# RF24_Node.net
KiCad netlist of a schematic drawn in EAGLE
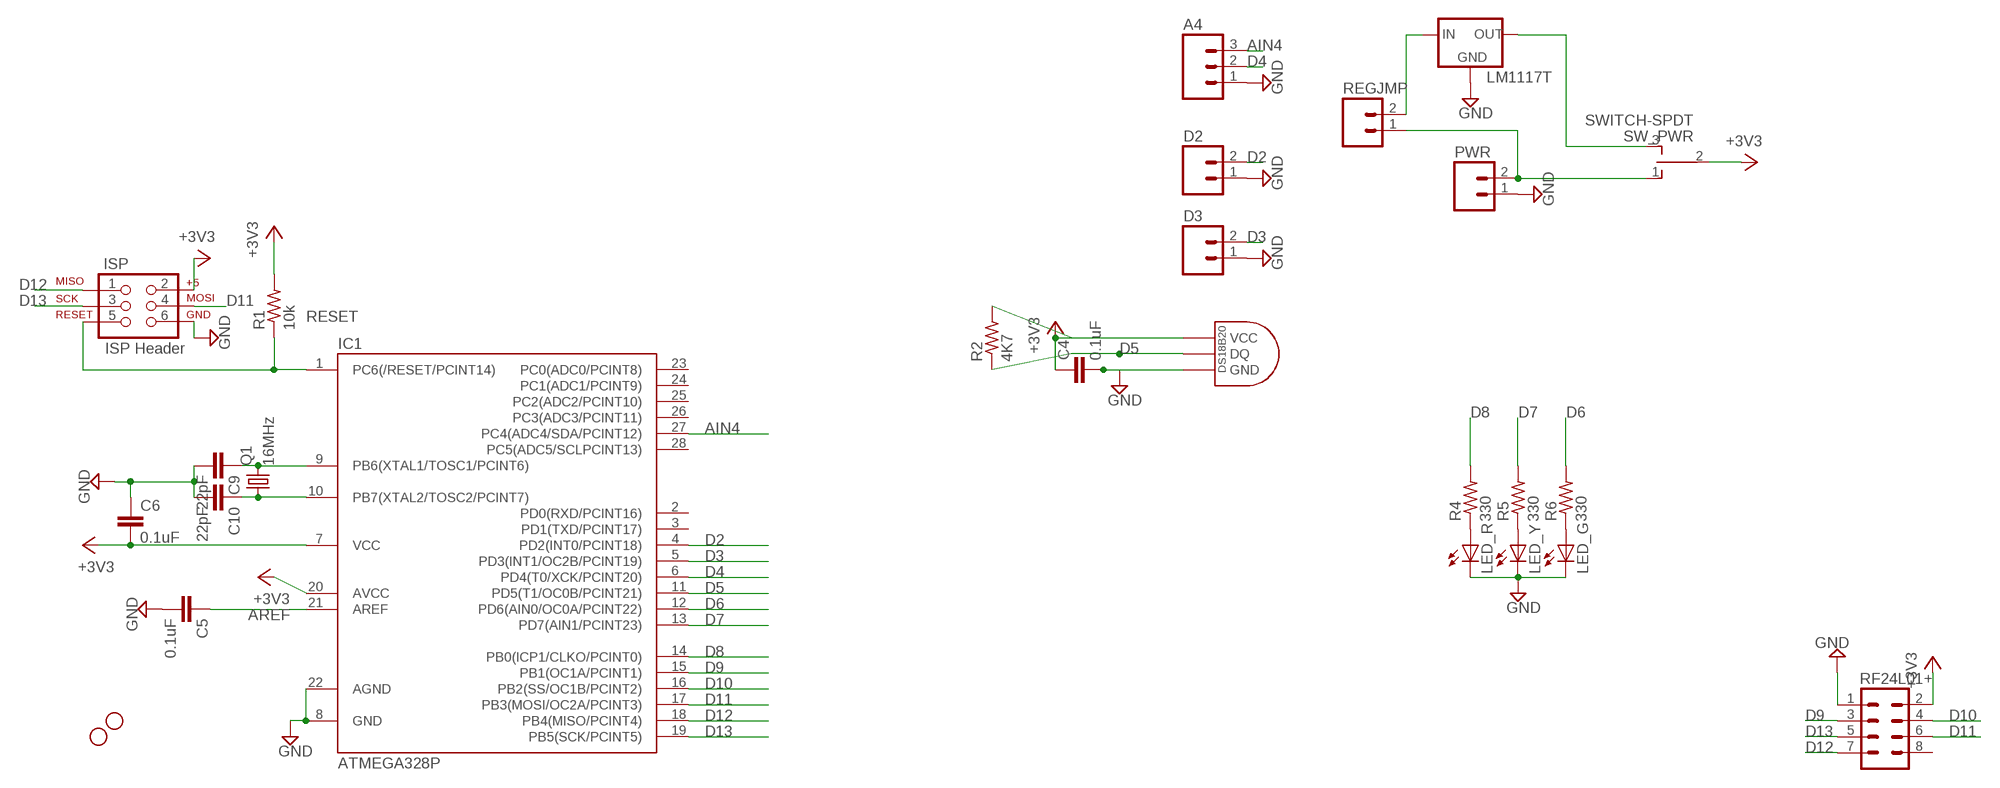
[diagram p0: schematic, sheet 1]

(export (version "E")
  (design (tool "Eeschema 10.0.6"))
  (components
    (comp (ref "A4")
      (value "M03PTH")
      (footprint "eagle-import:1X03")
      (libsource (lib "eagle-import") (part "M03PTH"))
    )
    (comp (ref "C4")
      (value "0.1uF")
      (footprint "eagle-import:C025-025X050")
      (libsource (lib "eagle-import") (part "C-EU025-025X050"))
    )
    (comp (ref "C5")
      (value "0.1uF")
      (footprint "eagle-import:C025-025X050")
      (libsource (lib "eagle-import") (part "C-EU025-025X050"))
    )
    (comp (ref "C6")
      (value "0.1uF")
      (footprint "eagle-import:C025-025X050")
      (libsource (lib "eagle-import") (part "C-EU025-025X050"))
    )
    (comp (ref "C9")
      (value "22pF")
      (footprint "eagle-import:C025-025X050")
      (libsource (lib "eagle-import") (part "C-EU025-025X050"))
    )
    (comp (ref "C10")
      (value "22pF")
      (footprint "eagle-import:C025-025X050")
      (libsource (lib "eagle-import") (part "C-EU025-025X050"))
    )
    (comp (ref "D2")
      (value "M02PTH")
      (footprint "eagle-import:1X02")
      (libsource (lib "eagle-import") (part "M02PTH"))
    )
    (comp (ref "D3")
      (value "M02PTH")
      (footprint "eagle-import:1X02")
      (libsource (lib "eagle-import") (part "M02PTH"))
    )
    (comp (ref "DS18B20")
      (value "DS1820TO92")
      (footprint "eagle-import:DS1820")
      (libsource (lib "eagle-import") (part "DS1820TO92"))
    )
    (comp (ref "IC1")
      (value "ATMEGA328P")
      (footprint "eagle-import:DIL28-3")
      (libsource (lib "eagle-import") (part "ATMEGA48/88/168-PU"))
    )
    (comp (ref "ISP")
      (value "ISP Header")
      (footprint "eagle-import:2X3")
      (libsource (lib "eagle-import") (part "AVR_SPI_PRG_6PTH"))
    )
    (comp (ref "JP2")
      (value "STAND-OFF")
      (footprint "eagle-import:STAND-OFF")
      (libsource (lib "eagle-import") (part "STAND-OFF"))
    )
    (comp (ref "JP8")
      (value "STAND-OFF")
      (footprint "eagle-import:STAND-OFF")
      (libsource (lib "eagle-import") (part "STAND-OFF"))
    )
    (comp (ref "LED_G")
      (value "LED3MM")
      (footprint "eagle-import:LED3MM")
      (libsource (lib "eagle-import") (part "LED3MM"))
    )
    (comp (ref "LED_R")
      (value "LED3MM")
      (footprint "eagle-import:LED3MM")
      (libsource (lib "eagle-import") (part "LED3MM"))
    )
    (comp (ref "LED_Y")
      (value "LED3MM")
      (footprint "eagle-import:LED3MM")
      (libsource (lib "eagle-import") (part "LED3MM"))
    )
    (comp (ref "LM1117T")
      (value "LM1117T-3.3-V")
      (footprint "eagle-import:TO220V")
      (libsource (lib "eagle-import") (part "LM1117T--V3.3"))
    )
    (comp (ref "PWR")
      (value "M02PTH")
      (footprint "eagle-import:1X02")
      (libsource (lib "eagle-import") (part "M02PTH"))
    )
    (comp (ref "Q1")
      (value "16MHz")
      (footprint "eagle-import:HC49_S")
      (libsource (lib "eagle-import") (part "CRYSTALHC49S"))
    )
    (comp (ref "R1")
      (value "10k")
      (footprint "eagle-import:0204V")
      (libsource (lib "eagle-import") (part "R-US_0204/2V"))
    )
    (comp (ref "R2")
      (value "4K7")
      (footprint "eagle-import:0204V")
      (libsource (lib "eagle-import") (part "R-US_0204/2V"))
    )
    (comp (ref "R4")
      (value "330")
      (footprint "eagle-import:0204V")
      (libsource (lib "eagle-import") (part "R-US_0204/2V"))
    )
    (comp (ref "R5")
      (value "330")
      (footprint "eagle-import:0204V")
      (libsource (lib "eagle-import") (part "R-US_0204/2V"))
    )
    (comp (ref "R6")
      (value "330")
      (footprint "eagle-import:0204V")
      (libsource (lib "eagle-import") (part "R-US_0204/2V"))
    )
    (comp (ref "REGJMP")
      (value "M02PTH")
      (footprint "eagle-import:1X02")
      (libsource (lib "eagle-import") (part "M02PTH"))
    )
    (comp (ref "RF24L01+")
      (value "M04X2")
      (footprint "eagle-import:2X4")
      (libsource (lib "eagle-import") (part "M04X2"))
    )
    (comp (ref "SW_PWR")
      (value "SWITCH-SPDT")
      (footprint "eagle-import:OS102011MS2QN1")
      (libsource (lib "eagle-import") (part "SWITCH-SPDT"))
    )
  )
  (nets
    (net (code "1") (name "+3V3") (class "Default")
      (node (ref "C4") (pin "1") (pinfunction "1_1") (pintype "passive"))
      (node (ref "C6") (pin "2") (pinfunction "2_2") (pintype "passive"))
      (node (ref "DS18B20") (pin "VDD") (pinfunction "VCC_VDD") (pintype "power_in"))
      (node (ref "IC1") (pin "20") (pinfunction "AVCC_20") (pintype "passive"))
      (node (ref "IC1") (pin "7") (pinfunction "VCC_7") (pintype "power_in"))
      (node (ref "ISP") (pin "2") (pinfunction "2_2") (pintype "passive"))
      (node (ref "R1") (pin "2") (pinfunction "2_2") (pintype "passive"))
      (node (ref "R2") (pin "2") (pinfunction "2_2") (pintype "passive"))
      (node (ref "RF24L01+") (pin "2") (pinfunction "2_2") (pintype "passive"))
      (node (ref "SW_PWR") (pin "2") (pinfunction "P_2") (pintype "passive"))
    )
    (net (code "2") (name "/AIN4") (class "Default")
      (node (ref "A4") (pin "3") (pinfunction "3_3") (pintype "passive"))
      (node (ref "IC1") (pin "27") (pinfunction "PC4(ADC4/SDA/PCINT12)_27") (pintype "bidirectional"))
    )
    (net (code "3") (name "/AREF") (class "Default")
      (node (ref "C5") (pin "1") (pinfunction "1_1") (pintype "passive"))
      (node (ref "IC1") (pin "21") (pinfunction "AREF_21") (pintype "passive"))
    )
    (net (code "4") (name "/D2") (class "Default")
      (node (ref "D2") (pin "2") (pinfunction "2_2") (pintype "passive"))
      (node (ref "IC1") (pin "4") (pinfunction "PD2(INT0/PCINT18)_4") (pintype "bidirectional"))
    )
    (net (code "5") (name "/D3") (class "Default")
      (node (ref "D3") (pin "2") (pinfunction "2_2") (pintype "passive"))
      (node (ref "IC1") (pin "5") (pinfunction "PD3(INT1/OC2B/PCINT19)_5") (pintype "bidirectional"))
    )
    (net (code "6") (name "/D4") (class "Default")
      (node (ref "A4") (pin "2") (pinfunction "2_2") (pintype "passive"))
      (node (ref "IC1") (pin "6") (pinfunction "PD4(T0/XCK/PCINT20)_6") (pintype "bidirectional"))
    )
    (net (code "7") (name "/D5") (class "Default")
      (node (ref "DS18B20") (pin "DQ") (pinfunction "DQ_DQ") (pintype "bidirectional"))
      (node (ref "IC1") (pin "11") (pinfunction "PD5(T1/OC0B/PCINT21)_11") (pintype "bidirectional"))
      (node (ref "R2") (pin "1") (pinfunction "1_1") (pintype "passive"))
    )
    (net (code "8") (name "/D6") (class "Default")
      (node (ref "IC1") (pin "12") (pinfunction "PD6(AIN0/OC0A/PCINT22)_12") (pintype "bidirectional"))
      (node (ref "R6") (pin "2") (pinfunction "2_2") (pintype "passive"))
    )
    (net (code "9") (name "/D7") (class "Default")
      (node (ref "IC1") (pin "13") (pinfunction "PD7(AIN1/PCINT23)_13") (pintype "bidirectional"))
      (node (ref "R5") (pin "2") (pinfunction "2_2") (pintype "passive"))
    )
    (net (code "10") (name "/D8") (class "Default")
      (node (ref "IC1") (pin "14") (pinfunction "PB0(ICP1/CLKO/PCINT0)_14") (pintype "bidirectional"))
      (node (ref "R4") (pin "2") (pinfunction "2_2") (pintype "passive"))
    )
    (net (code "11") (name "/D9") (class "Default")
      (node (ref "IC1") (pin "15") (pinfunction "PB1(OC1A/PCINT1)_15") (pintype "bidirectional"))
      (node (ref "RF24L01+") (pin "3") (pinfunction "3_3") (pintype "passive"))
    )
    (net (code "12") (name "/D10") (class "Default")
      (node (ref "IC1") (pin "16") (pinfunction "PB2(SS/OC1B/PCINT2)_16") (pintype "bidirectional"))
      (node (ref "RF24L01+") (pin "4") (pinfunction "4_4") (pintype "passive"))
    )
    (net (code "13") (name "/D11") (class "Default")
      (node (ref "IC1") (pin "17") (pinfunction "PB3(MOSI/OC2A/PCINT3)_17") (pintype "bidirectional"))
      (node (ref "ISP") (pin "4") (pinfunction "4_4") (pintype "passive"))
      (node (ref "RF24L01+") (pin "6") (pinfunction "6_6") (pintype "passive"))
    )
    (net (code "14") (name "/D12") (class "Default")
      (node (ref "IC1") (pin "18") (pinfunction "PB4(MISO/PCINT4)_18") (pintype "bidirectional"))
      (node (ref "ISP") (pin "1") (pinfunction "1_1") (pintype "passive"))
      (node (ref "RF24L01+") (pin "7") (pinfunction "7_7") (pintype "passive"))
    )
    (net (code "15") (name "/D13") (class "Default")
      (node (ref "IC1") (pin "19") (pinfunction "PB5(SCK/PCINT5)_19") (pintype "bidirectional"))
      (node (ref "ISP") (pin "3") (pinfunction "3_3") (pintype "passive"))
      (node (ref "RF24L01+") (pin "5") (pinfunction "5_5") (pintype "passive"))
    )
    (net (code "16") (name "/RESET") (class "Default")
      (node (ref "IC1") (pin "1") (pinfunction "PC6(/RESET/PCINT14)_1") (pintype "bidirectional"))
      (node (ref "ISP") (pin "5") (pinfunction "5_5") (pintype "passive"))
      (node (ref "R1") (pin "1") (pinfunction "1_1") (pintype "passive"))
    )
    (net (code "17") (name "GND") (class "Default")
      (node (ref "A4") (pin "1") (pinfunction "1_1") (pintype "passive"))
      (node (ref "C10") (pin "2") (pinfunction "2_2") (pintype "passive"))
      (node (ref "C4") (pin "2") (pinfunction "2_2") (pintype "passive"))
      (node (ref "C5") (pin "2") (pinfunction "2_2") (pintype "passive"))
      (node (ref "C6") (pin "1") (pinfunction "1_1") (pintype "passive"))
      (node (ref "C9") (pin "2") (pinfunction "2_2") (pintype "passive"))
      (node (ref "D2") (pin "1") (pinfunction "1_1") (pintype "passive"))
      (node (ref "D3") (pin "1") (pinfunction "1_1") (pintype "passive"))
      (node (ref "DS18B20") (pin "GND") (pinfunction "GND_GND") (pintype "power_in"))
      (node (ref "IC1") (pin "22") (pinfunction "AGND_22") (pintype "power_in"))
      (node (ref "IC1") (pin "8") (pinfunction "GND_8") (pintype "power_in"))
      (node (ref "ISP") (pin "6") (pinfunction "6_6") (pintype "passive"))
      (node (ref "LED_G") (pin "K") (pinfunction "C_K") (pintype "passive"))
      (node (ref "LED_R") (pin "K") (pinfunction "C_K") (pintype "passive"))
      (node (ref "LED_Y") (pin "K") (pinfunction "C_K") (pintype "passive"))
      (node (ref "LM1117T") (pin "1") (pinfunction "GND_1") (pintype "input"))
      (node (ref "PWR") (pin "1") (pinfunction "1_1") (pintype "passive"))
      (node (ref "RF24L01+") (pin "1") (pinfunction "1_1") (pintype "passive"))
    )
    (net (code "18") (name "Net-(IC1-PB6(XTAL1{slash}TOSC1{slash}PCINT6))") (class "Default")
      (node (ref "C9") (pin "1") (pinfunction "1_1") (pintype "passive"))
      (node (ref "IC1") (pin "9") (pinfunction "PB6(XTAL1/TOSC1/PCINT6)_9") (pintype "bidirectional"))
      (node (ref "Q1") (pin "2") (pinfunction "2_2") (pintype "passive"))
    )
    (net (code "19") (name "Net-(IC1-PB7(XTAL2{slash}TOSC2{slash}PCINT7))") (class "Default")
      (node (ref "C10") (pin "1") (pinfunction "1_1") (pintype "passive"))
      (node (ref "IC1") (pin "10") (pinfunction "PB7(XTAL2/TOSC2/PCINT7)_10") (pintype "bidirectional"))
      (node (ref "Q1") (pin "1") (pinfunction "1_1") (pintype "passive"))
    )
    (net (code "20") (name "Net-(LED_G-PadA)") (class "Default")
      (node (ref "LED_G") (pin "A") (pinfunction "A_A") (pintype "passive"))
      (node (ref "R6") (pin "1") (pinfunction "1_1") (pintype "passive"))
    )
    (net (code "21") (name "Net-(LED_R-PadA)") (class "Default")
      (node (ref "LED_R") (pin "A") (pinfunction "A_A") (pintype "passive"))
      (node (ref "R4") (pin "1") (pinfunction "1_1") (pintype "passive"))
    )
    (net (code "22") (name "Net-(LED_Y-PadA)") (class "Default")
      (node (ref "LED_Y") (pin "A") (pinfunction "A_A") (pintype "passive"))
      (node (ref "R5") (pin "1") (pinfunction "1_1") (pintype "passive"))
    )
    (net (code "23") (name "Net-(LM1117T-IN)") (class "Default")
      (node (ref "LM1117T") (pin "3") (pinfunction "IN_3") (pintype "input"))
      (node (ref "REGJMP") (pin "2") (pinfunction "2_2") (pintype "passive"))
    )
    (net (code "24") (name "Net-(LM1117T-OUT)") (class "Default")
      (node (ref "LM1117T") (pin "2") (pinfunction "OUT_2") (pintype "passive"))
      (node (ref "SW_PWR") (pin "3") (pinfunction "S_3") (pintype "passive"))
    )
    (net (code "25") (name "Net-(SW_PWR-O)") (class "Default")
      (node (ref "PWR") (pin "2") (pinfunction "2_2") (pintype "passive"))
      (node (ref "REGJMP") (pin "1") (pinfunction "1_1") (pintype "passive"))
      (node (ref "SW_PWR") (pin "1") (pinfunction "O_1") (pintype "passive"))
    )
    (net (code "26") (name "unconnected-(IC1-PC0(ADC0{slash}PCINT8)-Pad23)") (class "Default")
      (node (ref "IC1") (pin "23") (pinfunction "PC0(ADC0/PCINT8)_23") (pintype "bidirectional"))
    )
    (net (code "27") (name "unconnected-(IC1-PC1(ADC1{slash}PCINT9)-Pad24)") (class "Default")
      (node (ref "IC1") (pin "24") (pinfunction "PC1(ADC1/PCINT9)_24") (pintype "bidirectional"))
    )
    (net (code "28") (name "unconnected-(IC1-PC2(ADC2{slash}PCINT10)-Pad25)") (class "Default")
      (node (ref "IC1") (pin "25") (pinfunction "PC2(ADC2/PCINT10)_25") (pintype "bidirectional"))
    )
    (net (code "29") (name "unconnected-(IC1-PC3(ADC3{slash}PCINT11)-Pad26)") (class "Default")
      (node (ref "IC1") (pin "26") (pinfunction "PC3(ADC3/PCINT11)_26") (pintype "bidirectional"))
    )
    (net (code "30") (name "unconnected-(IC1-PC5(ADC5{slash}SCLPCINT13)-Pad28)") (class "Default")
      (node (ref "IC1") (pin "28") (pinfunction "PC5(ADC5/SCLPCINT13)_28") (pintype "bidirectional"))
    )
    (net (code "31") (name "unconnected-(IC1-PD0(RXD{slash}PCINT16)-Pad2)") (class "Default")
      (node (ref "IC1") (pin "2") (pinfunction "PD0(RXD/PCINT16)_2") (pintype "bidirectional"))
    )
    (net (code "32") (name "unconnected-(IC1-PD1(TXD{slash}PCINT17)-Pad3)") (class "Default")
      (node (ref "IC1") (pin "3") (pinfunction "PD1(TXD/PCINT17)_3") (pintype "bidirectional"))
    )
    (net (code "33") (name "unconnected-(RF24L01+-Pad8)") (class "Default")
      (node (ref "RF24L01+") (pin "8") (pinfunction "8_8") (pintype "passive"))
    )
  )
)
